# sine_wave_generator.net
KiCad netlist of a schematic drawn in Altium Designer
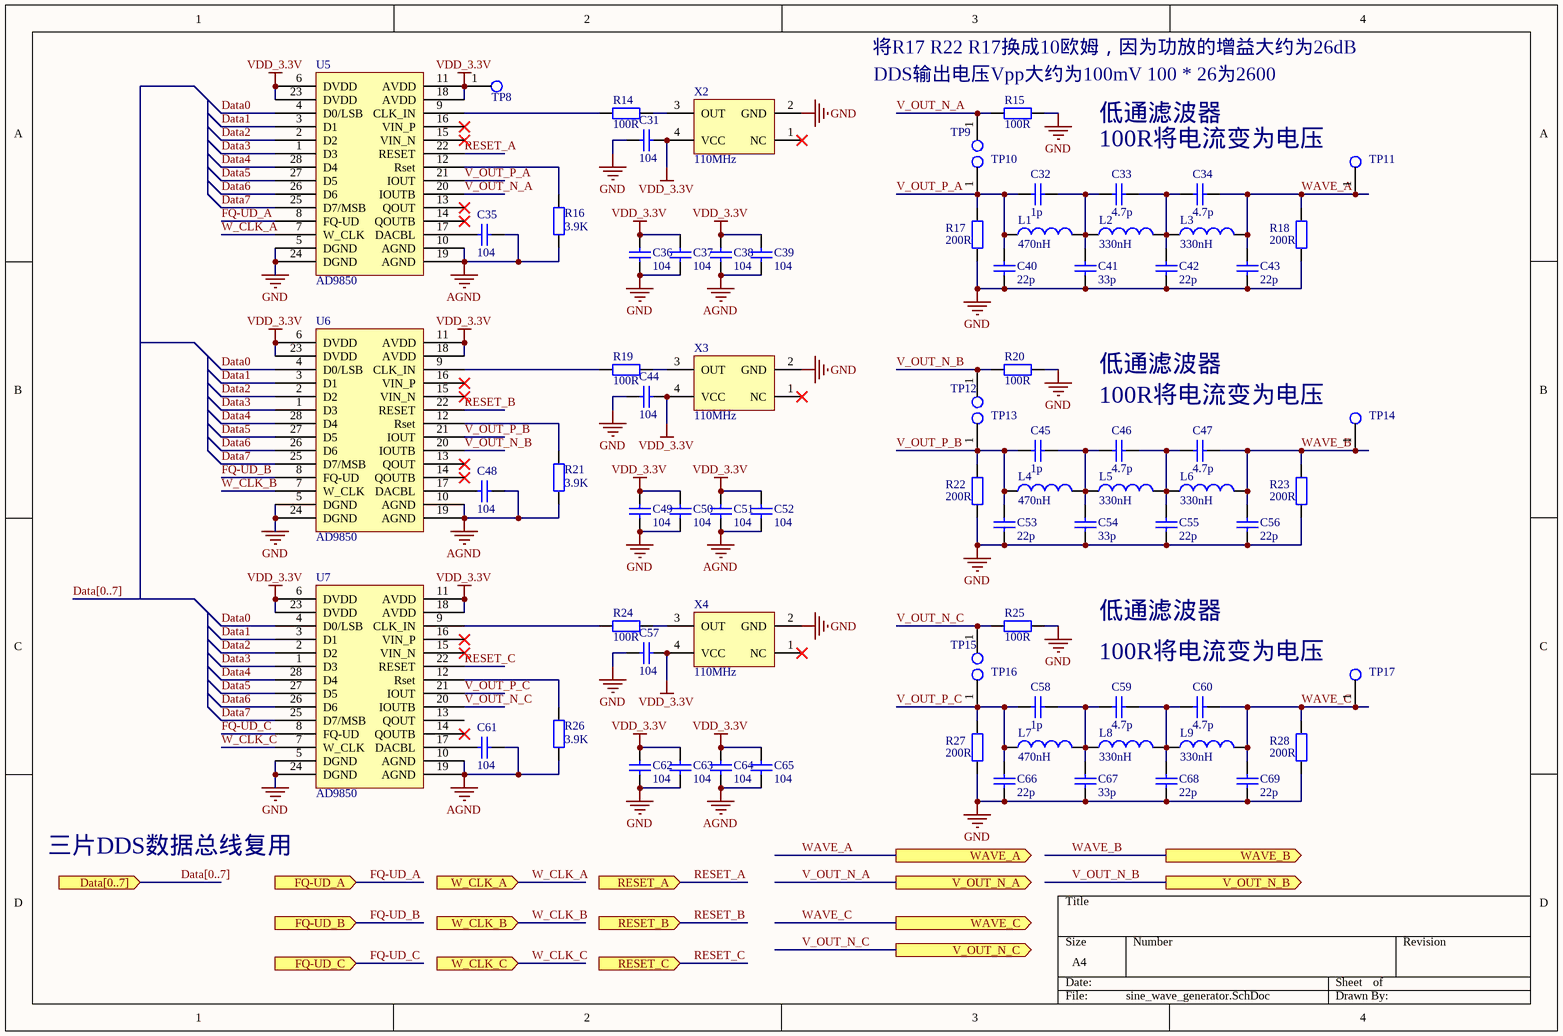
[diagram p0: sine_wave_generator.SchDoc]

(export (version "E")
  (design (tool "Eeschema 10.0.6"))
  (components
    (comp (ref "C31")
      (value "104")
      (footprint "0603")
      (fields (field (name "Comment") "Cap"))
      (libsource (lib "自动化研究所集成库20170318") (part "Cap"))
    )
    (comp (ref "C32")
      (value "1p")
      (footprint "0603")
      (fields (field (name "Comment") "Cap"))
      (libsource (lib "自动化研究所集成库20170318") (part "Cap"))
    )
    (comp (ref "C33")
      (value "4.7p")
      (footprint "0603")
      (fields (field (name "Comment") "Cap"))
      (libsource (lib "自动化研究所集成库20170318") (part "Cap"))
    )
    (comp (ref "C34")
      (value "4.7p")
      (footprint "0603")
      (fields (field (name "Comment") "Cap"))
      (libsource (lib "自动化研究所集成库20170318") (part "Cap"))
    )
    (comp (ref "C35")
      (value "104")
      (footprint "0603")
      (fields (field (name "Comment") "Cap"))
      (libsource (lib "自动化研究所集成库20170318") (part "Cap"))
    )
    (comp (ref "C36")
      (value "104")
      (footprint "0603")
      (fields (field (name "Comment") "Cap"))
      (libsource (lib "自动化研究所集成库20170318") (part "Cap"))
    )
    (comp (ref "C37")
      (value "104")
      (footprint "0603")
      (fields (field (name "Comment") "Cap"))
      (libsource (lib "自动化研究所集成库20170318") (part "Cap"))
    )
    (comp (ref "C38")
      (value "104")
      (footprint "0603")
      (fields (field (name "Comment") "Cap"))
      (libsource (lib "自动化研究所集成库20170318") (part "Cap"))
    )
    (comp (ref "C39")
      (value "104")
      (footprint "0603")
      (fields (field (name "Comment") "Cap"))
      (libsource (lib "自动化研究所集成库20170318") (part "Cap"))
    )
    (comp (ref "C40")
      (value "22p")
      (footprint "0603")
      (fields (field (name "Comment") "Cap"))
      (libsource (lib "自动化研究所集成库20170318") (part "Cap"))
    )
    (comp (ref "C41")
      (value "33p")
      (footprint "0603")
      (fields (field (name "Comment") "Cap"))
      (libsource (lib "自动化研究所集成库20170318") (part "Cap"))
    )
    (comp (ref "C42")
      (value "22p")
      (footprint "0603")
      (fields (field (name "Comment") "Cap"))
      (libsource (lib "自动化研究所集成库20170318") (part "Cap"))
    )
    (comp (ref "C43")
      (value "22p")
      (footprint "0603")
      (fields (field (name "Comment") "Cap"))
      (libsource (lib "自动化研究所集成库20170318") (part "Cap"))
    )
    (comp (ref "C44")
      (value "104")
      (footprint "0603")
      (fields (field (name "Comment") "Cap"))
      (libsource (lib "自动化研究所集成库20170318") (part "Cap"))
    )
    (comp (ref "C45")
      (value "1p")
      (footprint "0603")
      (fields (field (name "Comment") "Cap"))
      (libsource (lib "自动化研究所集成库20170318") (part "Cap"))
    )
    (comp (ref "C46")
      (value "4.7p")
      (footprint "0603")
      (fields (field (name "Comment") "Cap"))
      (libsource (lib "自动化研究所集成库20170318") (part "Cap"))
    )
    (comp (ref "C47")
      (value "4.7p")
      (footprint "0603")
      (fields (field (name "Comment") "Cap"))
      (libsource (lib "自动化研究所集成库20170318") (part "Cap"))
    )
    (comp (ref "C48")
      (value "104")
      (footprint "0603")
      (fields (field (name "Comment") "Cap"))
      (libsource (lib "自动化研究所集成库20170318") (part "Cap"))
    )
    (comp (ref "C49")
      (value "104")
      (footprint "0603")
      (fields (field (name "Comment") "Cap"))
      (libsource (lib "自动化研究所集成库20170318") (part "Cap"))
    )
    (comp (ref "C50")
      (value "104")
      (footprint "0603")
      (fields (field (name "Comment") "Cap"))
      (libsource (lib "自动化研究所集成库20170318") (part "Cap"))
    )
    (comp (ref "C51")
      (value "104")
      (footprint "0603")
      (fields (field (name "Comment") "Cap"))
      (libsource (lib "自动化研究所集成库20170318") (part "Cap"))
    )
    (comp (ref "C52")
      (value "104")
      (footprint "0603")
      (fields (field (name "Comment") "Cap"))
      (libsource (lib "自动化研究所集成库20170318") (part "Cap"))
    )
    (comp (ref "C53")
      (value "22p")
      (footprint "0603")
      (fields (field (name "Comment") "Cap"))
      (libsource (lib "自动化研究所集成库20170318") (part "Cap"))
    )
    (comp (ref "C54")
      (value "33p")
      (footprint "0603")
      (fields (field (name "Comment") "Cap"))
      (libsource (lib "自动化研究所集成库20170318") (part "Cap"))
    )
    (comp (ref "C55")
      (value "22p")
      (footprint "0603")
      (fields (field (name "Comment") "Cap"))
      (libsource (lib "自动化研究所集成库20170318") (part "Cap"))
    )
    (comp (ref "C56")
      (value "22p")
      (footprint "0603")
      (fields (field (name "Comment") "Cap"))
      (libsource (lib "自动化研究所集成库20170318") (part "Cap"))
    )
    (comp (ref "C57")
      (value "104")
      (footprint "0603")
      (fields (field (name "Comment") "Cap"))
      (libsource (lib "自动化研究所集成库20170318") (part "Cap"))
    )
    (comp (ref "C58")
      (value "1p")
      (footprint "0603")
      (fields (field (name "Comment") "Cap"))
      (libsource (lib "自动化研究所集成库20170318") (part "Cap"))
    )
    (comp (ref "C59")
      (value "4.7p")
      (footprint "0603")
      (fields (field (name "Comment") "Cap"))
      (libsource (lib "自动化研究所集成库20170318") (part "Cap"))
    )
    (comp (ref "C60")
      (value "4.7p")
      (footprint "0603")
      (fields (field (name "Comment") "Cap"))
      (libsource (lib "自动化研究所集成库20170318") (part "Cap"))
    )
    (comp (ref "C61")
      (value "104")
      (footprint "0603")
      (fields (field (name "Comment") "Cap"))
      (libsource (lib "自动化研究所集成库20170318") (part "Cap"))
    )
    (comp (ref "C62")
      (value "104")
      (footprint "0603")
      (fields (field (name "Comment") "Cap"))
      (libsource (lib "自动化研究所集成库20170318") (part "Cap"))
    )
    (comp (ref "C63")
      (value "104")
      (footprint "0603")
      (fields (field (name "Comment") "Cap"))
      (libsource (lib "自动化研究所集成库20170318") (part "Cap"))
    )
    (comp (ref "C64")
      (value "104")
      (footprint "0603")
      (fields (field (name "Comment") "Cap"))
      (libsource (lib "自动化研究所集成库20170318") (part "Cap"))
    )
    (comp (ref "C65")
      (value "104")
      (footprint "0603")
      (fields (field (name "Comment") "Cap"))
      (libsource (lib "自动化研究所集成库20170318") (part "Cap"))
    )
    (comp (ref "C66")
      (value "22p")
      (footprint "0603")
      (fields (field (name "Comment") "Cap"))
      (libsource (lib "自动化研究所集成库20170318") (part "Cap"))
    )
    (comp (ref "C67")
      (value "33p")
      (footprint "0603")
      (fields (field (name "Comment") "Cap"))
      (libsource (lib "自动化研究所集成库20170318") (part "Cap"))
    )
    (comp (ref "C68")
      (value "22p")
      (footprint "0603")
      (fields (field (name "Comment") "Cap"))
      (libsource (lib "自动化研究所集成库20170318") (part "Cap"))
    )
    (comp (ref "C69")
      (value "22p")
      (footprint "0603")
      (fields (field (name "Comment") "Cap"))
      (libsource (lib "自动化研究所集成库20170318") (part "Cap"))
    )
    (comp (ref "L1") (value "470nH") (footprint "0805L") (libsource (lib "Spartan") (part "Inductor")))
    (comp (ref "L2") (value "330nH") (footprint "0805L") (libsource (lib "Spartan") (part "Inductor")))
    (comp (ref "L3") (value "330nH") (footprint "0805L") (libsource (lib "Spartan") (part "Inductor")))
    (comp (ref "L4") (value "470nH") (footprint "0805L") (libsource (lib "Spartan") (part "Inductor")))
    (comp (ref "L5") (value "330nH") (footprint "0805L") (libsource (lib "Spartan") (part "Inductor")))
    (comp (ref "L6") (value "330nH") (footprint "0805L") (libsource (lib "Spartan") (part "Inductor")))
    (comp (ref "L7") (value "470nH") (footprint "0805L") (libsource (lib "Spartan") (part "Inductor")))
    (comp (ref "L8") (value "330nH") (footprint "0805L") (libsource (lib "Spartan") (part "Inductor")))
    (comp (ref "L9") (value "330nH") (footprint "0805L") (libsource (lib "Spartan") (part "Inductor")))
    (comp (ref "R14")
      (value "100R")
      (footprint "0603")
      (fields (field (name "Comment") "Res"))
      (libsource (lib "") (part "Res_1"))
    )
    (comp (ref "R15")
      (value "100R")
      (footprint "0603")
      (fields (field (name "Comment") "Res"))
      (libsource (lib "") (part "Res_1"))
    )
    (comp (ref "R16")
      (value "3.9K")
      (footprint "0603")
      (fields (field (name "Comment") "Res"))
      (libsource (lib "自动化研究所集成库20170318") (part "Res"))
    )
    (comp (ref "R17")
      (value "200R")
      (footprint "0603")
      (fields (field (name "Comment") "Res"))
      (libsource (lib "自动化研究所集成库20170318") (part "Res"))
    )
    (comp (ref "R18")
      (value "200R")
      (footprint "0603")
      (fields (field (name "Comment") "Res"))
      (libsource (lib "自动化研究所集成库20170318") (part "Res"))
    )
    (comp (ref "R19")
      (value "100R")
      (footprint "0603")
      (fields (field (name "Comment") "Res"))
      (libsource (lib "") (part "Res_1"))
    )
    (comp (ref "R20")
      (value "100R")
      (footprint "0603")
      (fields (field (name "Comment") "Res"))
      (libsource (lib "") (part "Res_1"))
    )
    (comp (ref "R21")
      (value "3.9K")
      (footprint "0603")
      (fields (field (name "Comment") "Res"))
      (libsource (lib "自动化研究所集成库20170318") (part "Res"))
    )
    (comp (ref "R22")
      (value "200R")
      (footprint "0603")
      (fields (field (name "Comment") "Res"))
      (libsource (lib "自动化研究所集成库20170318") (part "Res"))
    )
    (comp (ref "R23")
      (value "200R")
      (footprint "0603")
      (fields (field (name "Comment") "Res"))
      (libsource (lib "自动化研究所集成库20170318") (part "Res"))
    )
    (comp (ref "R24")
      (value "100R")
      (footprint "0603")
      (fields (field (name "Comment") "Res"))
      (libsource (lib "") (part "Res_1"))
    )
    (comp (ref "R25")
      (value "100R")
      (footprint "0603")
      (fields (field (name "Comment") "Res"))
      (libsource (lib "") (part "Res_1"))
    )
    (comp (ref "R26")
      (value "3.9K")
      (footprint "0603")
      (fields (field (name "Comment") "Res"))
      (libsource (lib "自动化研究所集成库20170318") (part "Res"))
    )
    (comp (ref "R27")
      (value "200R")
      (footprint "0603")
      (fields (field (name "Comment") "Res"))
      (libsource (lib "自动化研究所集成库20170318") (part "Res"))
    )
    (comp (ref "R28")
      (value "200R")
      (footprint "0603")
      (fields (field (name "Comment") "Res"))
      (libsource (lib "自动化研究所集成库20170318") (part "Res"))
    )
    (comp (ref "TP8") (value "testPoint") (footprint "TP_H") (libsource (lib "Spartan") (part "TP")))
    (comp (ref "TP9") (value "testPoint") (footprint "TP_H") (libsource (lib "Spartan") (part "TP")))
    (comp (ref "TP10") (value "testPoint") (footprint "TP_H") (libsource (lib "Spartan") (part "TP")))
    (comp (ref "TP11") (value "testPoint") (footprint "TP_H") (libsource (lib "Spartan") (part "TP")))
    (comp (ref "TP12") (value "testPoint") (footprint "TP_H") (libsource (lib "Spartan") (part "TP")))
    (comp (ref "TP13") (value "testPoint") (footprint "TP_H") (libsource (lib "Spartan") (part "TP")))
    (comp (ref "TP14") (value "testPoint") (footprint "TP_H") (libsource (lib "Spartan") (part "TP")))
    (comp (ref "TP15") (value "testPoint") (footprint "TP_H") (libsource (lib "Spartan") (part "TP")))
    (comp (ref "TP16") (value "testPoint") (footprint "TP_H") (libsource (lib "Spartan") (part "TP")))
    (comp (ref "TP17") (value "testPoint") (footprint "TP_H") (libsource (lib "Spartan") (part "TP")))
    (comp (ref "U5")
      (value "AD9850")
      (footprint "SOP65P780X198-28N")
      (libsource (lib "Dugu") (part "AD9850"))
    )
    (comp (ref "U6")
      (value "AD9850")
      (footprint "SOP65P780X198-28N")
      (libsource (lib "Dugu") (part "AD9850"))
    )
    (comp (ref "U7")
      (value "AD9850")
      (footprint "SOP65P780X198-28N")
      (libsource (lib "Dugu") (part "AD9850"))
    )
    (comp (ref "X2")
      (value "110MHz")
      (footprint "3225")
      (libsource (lib "PulsePower-Buck") (part "Oscillator"))
    )
    (comp (ref "X3")
      (value "110MHz")
      (footprint "3225")
      (libsource (lib "PulsePower-Buck") (part "Oscillator"))
    )
    (comp (ref "X4")
      (value "110MHz")
      (footprint "3225")
      (libsource (lib "PulsePower-Buck") (part "Oscillator"))
    )
  )
  (nets
    (net (code "1") (name "/Data0") (class "Default")
      (node (ref "U5") (pin "4") (pinfunction "D0/LSB_4") (pintype "passive"))
      (node (ref "U6") (pin "4") (pinfunction "D0/LSB_4") (pintype "passive"))
      (node (ref "U7") (pin "4") (pinfunction "D0/LSB_4") (pintype "passive"))
    )
    (net (code "2") (name "/Data1") (class "Default")
      (node (ref "U5") (pin "3") (pinfunction "D1_3") (pintype "passive"))
      (node (ref "U6") (pin "3") (pinfunction "D1_3") (pintype "passive"))
      (node (ref "U7") (pin "3") (pinfunction "D1_3") (pintype "passive"))
    )
    (net (code "3") (name "/Data2") (class "Default")
      (node (ref "U5") (pin "2") (pinfunction "D2_2") (pintype "passive"))
      (node (ref "U6") (pin "2") (pinfunction "D2_2") (pintype "passive"))
      (node (ref "U7") (pin "2") (pinfunction "D2_2") (pintype "passive"))
    )
    (net (code "4") (name "/Data3") (class "Default")
      (node (ref "U5") (pin "1") (pinfunction "D3_1") (pintype "passive"))
      (node (ref "U6") (pin "1") (pinfunction "D3_1") (pintype "passive"))
      (node (ref "U7") (pin "1") (pinfunction "D3_1") (pintype "passive"))
    )
    (net (code "5") (name "/Data4") (class "Default")
      (node (ref "U5") (pin "28") (pinfunction "D4_28") (pintype "passive"))
      (node (ref "U6") (pin "28") (pinfunction "D4_28") (pintype "passive"))
      (node (ref "U7") (pin "28") (pinfunction "D4_28") (pintype "passive"))
    )
    (net (code "6") (name "/Data5") (class "Default")
      (node (ref "U5") (pin "27") (pinfunction "D5_27") (pintype "passive"))
      (node (ref "U6") (pin "27") (pinfunction "D5_27") (pintype "passive"))
      (node (ref "U7") (pin "27") (pinfunction "D5_27") (pintype "passive"))
    )
    (net (code "7") (name "/Data6") (class "Default")
      (node (ref "U5") (pin "26") (pinfunction "D6_26") (pintype "passive"))
      (node (ref "U6") (pin "26") (pinfunction "D6_26") (pintype "passive"))
      (node (ref "U7") (pin "26") (pinfunction "D6_26") (pintype "passive"))
    )
    (net (code "8") (name "/Data7") (class "Default")
      (node (ref "U5") (pin "25") (pinfunction "D7/MSB_25") (pintype "passive"))
      (node (ref "U6") (pin "25") (pinfunction "D7/MSB_25") (pintype "passive"))
      (node (ref "U7") (pin "25") (pinfunction "D7/MSB_25") (pintype "passive"))
    )
    (net (code "10") (name "/FQ-UD_A") (class "Default")
      (node (ref "U5") (pin "8") (pinfunction "FQ-UD_8") (pintype "passive"))
    )
    (net (code "11") (name "/FQ-UD_B") (class "Default")
      (node (ref "U6") (pin "8") (pinfunction "FQ-UD_8") (pintype "passive"))
    )
    (net (code "12") (name "/FQ-UD_C") (class "Default")
      (node (ref "U7") (pin "8") (pinfunction "FQ-UD_8") (pintype "passive"))
    )
    (net (code "13") (name "/RESET_A") (class "Default")
      (node (ref "U5") (pin "22") (pinfunction "RESET_22") (pintype "passive"))
    )
    (net (code "14") (name "/RESET_B") (class "Default")
      (node (ref "U6") (pin "22") (pinfunction "RESET_22") (pintype "passive"))
    )
    (net (code "15") (name "/RESET_C") (class "Default")
      (node (ref "U7") (pin "22") (pinfunction "RESET_22") (pintype "passive"))
    )
    (net (code "16") (name "/V_OUT_N_A") (class "Default")
      (node (ref "R15") (pin "1") (pinfunction "1_1") (pintype "passive"))
      (node (ref "TP9") (pin "1") (pinfunction "1_1") (pintype "passive"))
      (node (ref "U5") (pin "20") (pinfunction "IOUTB_20") (pintype "passive"))
    )
    (net (code "17") (name "/V_OUT_N_B") (class "Default")
      (node (ref "R20") (pin "1") (pinfunction "1_1") (pintype "passive"))
      (node (ref "TP12") (pin "1") (pinfunction "1_1") (pintype "passive"))
      (node (ref "U6") (pin "20") (pinfunction "IOUTB_20") (pintype "passive"))
    )
    (net (code "18") (name "/V_OUT_N_C") (class "Default")
      (node (ref "R25") (pin "1") (pinfunction "1_1") (pintype "passive"))
      (node (ref "TP15") (pin "1") (pinfunction "1_1") (pintype "passive"))
      (node (ref "U7") (pin "20") (pinfunction "IOUTB_20") (pintype "passive"))
    )
    (net (code "19") (name "/V_OUT_P_A") (class "Default")
      (node (ref "C32") (pin "1") (pinfunction "1_1") (pintype "passive"))
      (node (ref "C40") (pin "2") (pinfunction "2_2") (pintype "passive"))
      (node (ref "L1") (pin "1") (pinfunction "1_1") (pintype "passive"))
      (node (ref "R17") (pin "2") (pinfunction "2_2") (pintype "passive"))
      (node (ref "TP10") (pin "1") (pinfunction "1_1") (pintype "passive"))
      (node (ref "U5") (pin "21") (pinfunction "IOUT_21") (pintype "passive"))
    )
    (net (code "20") (name "/V_OUT_P_B") (class "Default")
      (node (ref "C45") (pin "1") (pinfunction "1_1") (pintype "passive"))
      (node (ref "C53") (pin "2") (pinfunction "2_2") (pintype "passive"))
      (node (ref "L4") (pin "1") (pinfunction "1_1") (pintype "passive"))
      (node (ref "R22") (pin "2") (pinfunction "2_2") (pintype "passive"))
      (node (ref "TP13") (pin "1") (pinfunction "1_1") (pintype "passive"))
      (node (ref "U6") (pin "21") (pinfunction "IOUT_21") (pintype "passive"))
    )
    (net (code "21") (name "/V_OUT_P_C") (class "Default")
      (node (ref "C58") (pin "1") (pinfunction "1_1") (pintype "passive"))
      (node (ref "C66") (pin "2") (pinfunction "2_2") (pintype "passive"))
      (node (ref "L7") (pin "1") (pinfunction "1_1") (pintype "passive"))
      (node (ref "R27") (pin "2") (pinfunction "2_2") (pintype "passive"))
      (node (ref "TP16") (pin "1") (pinfunction "1_1") (pintype "passive"))
      (node (ref "U7") (pin "21") (pinfunction "IOUT_21") (pintype "passive"))
    )
    (net (code "22") (name "/WAVE_A") (class "Default")
      (node (ref "C34") (pin "2") (pinfunction "2_2") (pintype "passive"))
      (node (ref "C43") (pin "2") (pinfunction "2_2") (pintype "passive"))
      (node (ref "L3") (pin "2") (pinfunction "2_2") (pintype "passive"))
      (node (ref "R18") (pin "2") (pinfunction "2_2") (pintype "passive"))
      (node (ref "TP11") (pin "1") (pinfunction "1_1") (pintype "passive"))
    )
    (net (code "23") (name "/WAVE_B") (class "Default")
      (node (ref "C47") (pin "2") (pinfunction "2_2") (pintype "passive"))
      (node (ref "C56") (pin "2") (pinfunction "2_2") (pintype "passive"))
      (node (ref "L6") (pin "2") (pinfunction "2_2") (pintype "passive"))
      (node (ref "R23") (pin "2") (pinfunction "2_2") (pintype "passive"))
      (node (ref "TP14") (pin "1") (pinfunction "1_1") (pintype "passive"))
    )
    (net (code "24") (name "/WAVE_C") (class "Default")
      (node (ref "C60") (pin "2") (pinfunction "2_2") (pintype "passive"))
      (node (ref "C69") (pin "2") (pinfunction "2_2") (pintype "passive"))
      (node (ref "L9") (pin "2") (pinfunction "2_2") (pintype "passive"))
      (node (ref "R28") (pin "2") (pinfunction "2_2") (pintype "passive"))
      (node (ref "TP17") (pin "1") (pinfunction "1_1") (pintype "passive"))
    )
    (net (code "25") (name "/W_CLK_A") (class "Default")
      (node (ref "U5") (pin "7") (pinfunction "W_CLK_7") (pintype "passive"))
    )
    (net (code "26") (name "/W_CLK_B") (class "Default")
      (node (ref "U6") (pin "7") (pinfunction "W_CLK_7") (pintype "passive"))
    )
    (net (code "27") (name "/W_CLK_C") (class "Default")
      (node (ref "U7") (pin "7") (pinfunction "W_CLK_7") (pintype "passive"))
    )
    (net (code "28") (name "AGND") (class "Default")
      (node (ref "C35") (pin "2") (pinfunction "2_2") (pintype "passive"))
      (node (ref "C38") (pin "1") (pinfunction "1_1") (pintype "passive"))
      (node (ref "C39") (pin "1") (pinfunction "1_1") (pintype "passive"))
      (node (ref "C48") (pin "2") (pinfunction "2_2") (pintype "passive"))
      (node (ref "C51") (pin "1") (pinfunction "1_1") (pintype "passive"))
      (node (ref "C52") (pin "1") (pinfunction "1_1") (pintype "passive"))
      (node (ref "C61") (pin "1") (pinfunction "1_1") (pintype "passive"))
      (node (ref "C64") (pin "1") (pinfunction "1_1") (pintype "passive"))
      (node (ref "C65") (pin "1") (pinfunction "1_1") (pintype "passive"))
      (node (ref "R16") (pin "1") (pinfunction "1_1") (pintype "passive"))
      (node (ref "R21") (pin "1") (pinfunction "1_1") (pintype "passive"))
      (node (ref "R26") (pin "1") (pinfunction "1_1") (pintype "passive"))
      (node (ref "U5") (pin "10") (pinfunction "AGND_10") (pintype "power_in"))
      (node (ref "U5") (pin "19") (pinfunction "AGND_19") (pintype "passive"))
      (node (ref "U6") (pin "10") (pinfunction "AGND_10") (pintype "power_in"))
      (node (ref "U6") (pin "19") (pinfunction "AGND_19") (pintype "passive"))
      (node (ref "U7") (pin "10") (pinfunction "AGND_10") (pintype "power_in"))
      (node (ref "U7") (pin "19") (pinfunction "AGND_19") (pintype "passive"))
    )
    (net (code "29") (name "GND") (class "Default")
      (node (ref "C31") (pin "1") (pinfunction "1_1") (pintype "passive"))
      (node (ref "C36") (pin "1") (pinfunction "1_1") (pintype "passive"))
      (node (ref "C37") (pin "1") (pinfunction "1_1") (pintype "passive"))
      (node (ref "C40") (pin "1") (pinfunction "1_1") (pintype "passive"))
      (node (ref "C41") (pin "1") (pinfunction "1_1") (pintype "passive"))
      (node (ref "C42") (pin "1") (pinfunction "1_1") (pintype "passive"))
      (node (ref "C43") (pin "1") (pinfunction "1_1") (pintype "passive"))
      (node (ref "C44") (pin "1") (pinfunction "1_1") (pintype "passive"))
      (node (ref "C49") (pin "1") (pinfunction "1_1") (pintype "passive"))
      (node (ref "C50") (pin "1") (pinfunction "1_1") (pintype "passive"))
      (node (ref "C53") (pin "1") (pinfunction "1_1") (pintype "passive"))
      (node (ref "C54") (pin "1") (pinfunction "1_1") (pintype "passive"))
      (node (ref "C55") (pin "1") (pinfunction "1_1") (pintype "passive"))
      (node (ref "C56") (pin "1") (pinfunction "1_1") (pintype "passive"))
      (node (ref "C57") (pin "2") (pinfunction "2_2") (pintype "passive"))
      (node (ref "C62") (pin "1") (pinfunction "1_1") (pintype "passive"))
      (node (ref "C63") (pin "1") (pinfunction "1_1") (pintype "passive"))
      (node (ref "C66") (pin "1") (pinfunction "1_1") (pintype "passive"))
      (node (ref "C67") (pin "1") (pinfunction "1_1") (pintype "passive"))
      (node (ref "C68") (pin "1") (pinfunction "1_1") (pintype "passive"))
      (node (ref "C69") (pin "1") (pinfunction "1_1") (pintype "passive"))
      (node (ref "R15") (pin "2") (pinfunction "2_2") (pintype "passive"))
      (node (ref "R17") (pin "1") (pinfunction "1_1") (pintype "passive"))
      (node (ref "R18") (pin "1") (pinfunction "1_1") (pintype "passive"))
      (node (ref "R20") (pin "2") (pinfunction "2_2") (pintype "passive"))
      (node (ref "R22") (pin "1") (pinfunction "1_1") (pintype "passive"))
      (node (ref "R23") (pin "1") (pinfunction "1_1") (pintype "passive"))
      (node (ref "R25") (pin "2") (pinfunction "2_2") (pintype "passive"))
      (node (ref "R27") (pin "1") (pinfunction "1_1") (pintype "passive"))
      (node (ref "R28") (pin "1") (pinfunction "1_1") (pintype "passive"))
      (node (ref "U5") (pin "24") (pinfunction "DGND_24") (pintype "passive"))
      (node (ref "U5") (pin "5") (pinfunction "DGND_5") (pintype "passive"))
      (node (ref "U6") (pin "24") (pinfunction "DGND_24") (pintype "passive"))
      (node (ref "U6") (pin "5") (pinfunction "DGND_5") (pintype "passive"))
      (node (ref "U7") (pin "24") (pinfunction "DGND_24") (pintype "passive"))
      (node (ref "U7") (pin "5") (pinfunction "DGND_5") (pintype "passive"))
      (node (ref "X2") (pin "2") (pinfunction "GND_2") (pintype "passive"))
      (node (ref "X3") (pin "2") (pinfunction "GND_2") (pintype "passive"))
      (node (ref "X4") (pin "2") (pinfunction "GND_2") (pintype "passive"))
    )
    (net (code "30") (name "Net-(C32-Pad2)") (class "Default")
      (node (ref "C32") (pin "2") (pinfunction "2_2") (pintype "passive"))
      (node (ref "C33") (pin "1") (pinfunction "1_1") (pintype "passive"))
      (node (ref "C41") (pin "2") (pinfunction "2_2") (pintype "passive"))
      (node (ref "L1") (pin "2") (pinfunction "2_2") (pintype "passive"))
      (node (ref "L2") (pin "1") (pinfunction "1_1") (pintype "passive"))
    )
    (net (code "31") (name "Net-(C33-Pad2)") (class "Default")
      (node (ref "C33") (pin "2") (pinfunction "2_2") (pintype "passive"))
      (node (ref "C34") (pin "1") (pinfunction "1_1") (pintype "passive"))
      (node (ref "C42") (pin "2") (pinfunction "2_2") (pintype "passive"))
      (node (ref "L2") (pin "2") (pinfunction "2_2") (pintype "passive"))
      (node (ref "L3") (pin "1") (pinfunction "1_1") (pintype "passive"))
    )
    (net (code "32") (name "Net-(C45-Pad2)") (class "Default")
      (node (ref "C45") (pin "2") (pinfunction "2_2") (pintype "passive"))
      (node (ref "C46") (pin "1") (pinfunction "1_1") (pintype "passive"))
      (node (ref "C54") (pin "2") (pinfunction "2_2") (pintype "passive"))
      (node (ref "L4") (pin "2") (pinfunction "2_2") (pintype "passive"))
      (node (ref "L5") (pin "1") (pinfunction "1_1") (pintype "passive"))
    )
    (net (code "33") (name "Net-(C46-Pad2)") (class "Default")
      (node (ref "C46") (pin "2") (pinfunction "2_2") (pintype "passive"))
      (node (ref "C47") (pin "1") (pinfunction "1_1") (pintype "passive"))
      (node (ref "C55") (pin "2") (pinfunction "2_2") (pintype "passive"))
      (node (ref "L5") (pin "2") (pinfunction "2_2") (pintype "passive"))
      (node (ref "L6") (pin "1") (pinfunction "1_1") (pintype "passive"))
    )
    (net (code "34") (name "Net-(C58-Pad2)") (class "Default")
      (node (ref "C58") (pin "2") (pinfunction "2_2") (pintype "passive"))
      (node (ref "C59") (pin "1") (pinfunction "1_1") (pintype "passive"))
      (node (ref "C67") (pin "2") (pinfunction "2_2") (pintype "passive"))
      (node (ref "L7") (pin "2") (pinfunction "2_2") (pintype "passive"))
      (node (ref "L8") (pin "1") (pinfunction "1_1") (pintype "passive"))
    )
    (net (code "35") (name "Net-(C59-Pad2)") (class "Default")
      (node (ref "C59") (pin "2") (pinfunction "2_2") (pintype "passive"))
      (node (ref "C60") (pin "1") (pinfunction "1_1") (pintype "passive"))
      (node (ref "C68") (pin "2") (pinfunction "2_2") (pintype "passive"))
      (node (ref "L8") (pin "2") (pinfunction "2_2") (pintype "passive"))
      (node (ref "L9") (pin "1") (pinfunction "1_1") (pintype "passive"))
    )
    (net (code "36") (name "Net-(U5-CLK_IN)") (class "Default")
      (node (ref "R14") (pin "1") (pinfunction "1_1") (pintype "passive"))
      (node (ref "U5") (pin "9") (pinfunction "CLK_IN_9") (pintype "passive"))
    )
    (net (code "37") (name "Net-(U5-DACBL)") (class "Default")
      (node (ref "C35") (pin "1") (pinfunction "1_1") (pintype "passive"))
      (node (ref "U5") (pin "17") (pinfunction "DACBL_17") (pintype "passive"))
    )
    (net (code "38") (name "Net-(U5-Rset)") (class "Default")
      (node (ref "R16") (pin "2") (pinfunction "2_2") (pintype "passive"))
      (node (ref "U5") (pin "12") (pinfunction "Rset_12") (pintype "passive"))
    )
    (net (code "39") (name "Net-(U6-CLK_IN)") (class "Default")
      (node (ref "R19") (pin "1") (pinfunction "1_1") (pintype "passive"))
      (node (ref "U6") (pin "9") (pinfunction "CLK_IN_9") (pintype "passive"))
    )
    (net (code "40") (name "Net-(U6-DACBL)") (class "Default")
      (node (ref "C48") (pin "1") (pinfunction "1_1") (pintype "passive"))
      (node (ref "U6") (pin "17") (pinfunction "DACBL_17") (pintype "passive"))
    )
    (net (code "41") (name "Net-(U6-Rset)") (class "Default")
      (node (ref "R21") (pin "2") (pinfunction "2_2") (pintype "passive"))
      (node (ref "U6") (pin "12") (pinfunction "Rset_12") (pintype "passive"))
    )
    (net (code "42") (name "Net-(U7-CLK_IN)") (class "Default")
      (node (ref "R24") (pin "1") (pinfunction "1_1") (pintype "passive"))
      (node (ref "U7") (pin "9") (pinfunction "CLK_IN_9") (pintype "passive"))
    )
    (net (code "43") (name "Net-(U7-DACBL)") (class "Default")
      (node (ref "C61") (pin "2") (pinfunction "2_2") (pintype "passive"))
      (node (ref "U7") (pin "17") (pinfunction "DACBL_17") (pintype "passive"))
    )
    (net (code "44") (name "Net-(U7-Rset)") (class "Default")
      (node (ref "R26") (pin "2") (pinfunction "2_2") (pintype "passive"))
      (node (ref "U7") (pin "12") (pinfunction "Rset_12") (pintype "passive"))
    )
    (net (code "45") (name "Net-(X2-OUT)") (class "Default")
      (node (ref "R14") (pin "2") (pinfunction "2_2") (pintype "passive"))
      (node (ref "X2") (pin "3") (pinfunction "OUT_3") (pintype "passive"))
    )
    (net (code "46") (name "Net-(X3-OUT)") (class "Default")
      (node (ref "R19") (pin "2") (pinfunction "2_2") (pintype "passive"))
      (node (ref "X3") (pin "3") (pinfunction "OUT_3") (pintype "passive"))
    )
    (net (code "47") (name "Net-(X4-OUT)") (class "Default")
      (node (ref "R24") (pin "2") (pinfunction "2_2") (pintype "passive"))
      (node (ref "X4") (pin "3") (pinfunction "OUT_3") (pintype "passive"))
    )
    (net (code "48") (name "VDD_3.3V") (class "Default")
      (node (ref "C31") (pin "2") (pinfunction "2_2") (pintype "passive"))
      (node (ref "C36") (pin "2") (pinfunction "2_2") (pintype "passive"))
      (node (ref "C37") (pin "2") (pinfunction "2_2") (pintype "passive"))
      (node (ref "C38") (pin "2") (pinfunction "2_2") (pintype "passive"))
      (node (ref "C39") (pin "2") (pinfunction "2_2") (pintype "passive"))
      (node (ref "C44") (pin "2") (pinfunction "2_2") (pintype "passive"))
      (node (ref "C49") (pin "2") (pinfunction "2_2") (pintype "passive"))
      (node (ref "C50") (pin "2") (pinfunction "2_2") (pintype "passive"))
      (node (ref "C51") (pin "2") (pinfunction "2_2") (pintype "passive"))
      (node (ref "C52") (pin "2") (pinfunction "2_2") (pintype "passive"))
      (node (ref "C57") (pin "1") (pinfunction "1_1") (pintype "passive"))
      (node (ref "C62") (pin "2") (pinfunction "2_2") (pintype "passive"))
      (node (ref "C63") (pin "2") (pinfunction "2_2") (pintype "passive"))
      (node (ref "C64") (pin "2") (pinfunction "2_2") (pintype "passive"))
      (node (ref "C65") (pin "2") (pinfunction "2_2") (pintype "passive"))
      (node (ref "TP8") (pin "1") (pinfunction "1_1") (pintype "passive"))
      (node (ref "U5") (pin "11") (pinfunction "AVDD_11") (pintype "passive"))
      (node (ref "U5") (pin "18") (pinfunction "AVDD_18") (pintype "passive"))
      (node (ref "U5") (pin "23") (pinfunction "DVDD_23") (pintype "passive"))
      (node (ref "U5") (pin "6") (pinfunction "DVDD_6") (pintype "passive"))
      (node (ref "U6") (pin "11") (pinfunction "AVDD_11") (pintype "passive"))
      (node (ref "U6") (pin "18") (pinfunction "AVDD_18") (pintype "passive"))
      (node (ref "U6") (pin "23") (pinfunction "DVDD_23") (pintype "passive"))
      (node (ref "U6") (pin "6") (pinfunction "DVDD_6") (pintype "passive"))
      (node (ref "U7") (pin "11") (pinfunction "AVDD_11") (pintype "passive"))
      (node (ref "U7") (pin "18") (pinfunction "AVDD_18") (pintype "passive"))
      (node (ref "U7") (pin "23") (pinfunction "DVDD_23") (pintype "passive"))
      (node (ref "U7") (pin "6") (pinfunction "DVDD_6") (pintype "passive"))
      (node (ref "X2") (pin "4") (pinfunction "VCC_4") (pintype "passive"))
      (node (ref "X3") (pin "4") (pinfunction "VCC_4") (pintype "passive"))
      (node (ref "X4") (pin "4") (pinfunction "VCC_4") (pintype "passive"))
    )
    (net (code "49") (name "unconnected-(U5-QOUT-Pad13)") (class "Default")
      (node (ref "U5") (pin "13") (pinfunction "QOUT_13") (pintype "passive+no_connect"))
    )
    (net (code "50") (name "unconnected-(U5-QOUTB-Pad14)") (class "Default")
      (node (ref "U5") (pin "14") (pinfunction "QOUTB_14") (pintype "passive+no_connect"))
    )
    (net (code "51") (name "unconnected-(U5-VIN_N-Pad15)") (class "Default")
      (node (ref "U5") (pin "15") (pinfunction "VIN_N_15") (pintype "passive+no_connect"))
    )
    (net (code "52") (name "unconnected-(U5-VIN_P-Pad16)") (class "Default")
      (node (ref "U5") (pin "16") (pinfunction "VIN_P_16") (pintype "passive+no_connect"))
    )
    (net (code "53") (name "unconnected-(U6-QOUT-Pad13)") (class "Default")
      (node (ref "U6") (pin "13") (pinfunction "QOUT_13") (pintype "passive+no_connect"))
    )
    (net (code "54") (name "unconnected-(U6-QOUTB-Pad14)") (class "Default")
      (node (ref "U6") (pin "14") (pinfunction "QOUTB_14") (pintype "passive+no_connect"))
    )
    (net (code "55") (name "unconnected-(U6-VIN_N-Pad15)") (class "Default")
      (node (ref "U6") (pin "15") (pinfunction "VIN_N_15") (pintype "passive+no_connect"))
    )
    (net (code "56") (name "unconnected-(U6-VIN_P-Pad16)") (class "Default")
      (node (ref "U6") (pin "16") (pinfunction "VIN_P_16") (pintype "passive+no_connect"))
    )
    (net (code "57") (name "unconnected-(U7-QOUT-Pad13)") (class "Default")
      (node (ref "U7") (pin "13") (pinfunction "QOUT_13") (pintype "passive"))
    )
    (net (code "58") (name "unconnected-(U7-QOUTB-Pad14)") (class "Default")
      (node (ref "U7") (pin "14") (pinfunction "QOUTB_14") (pintype "passive+no_connect"))
    )
    (net (code "59") (name "unconnected-(U7-VIN_N-Pad15)") (class "Default")
      (node (ref "U7") (pin "15") (pinfunction "VIN_N_15") (pintype "passive+no_connect"))
    )
    (net (code "60") (name "unconnected-(U7-VIN_P-Pad16)") (class "Default")
      (node (ref "U7") (pin "16") (pinfunction "VIN_P_16") (pintype "passive+no_connect"))
    )
    (net (code "61") (name "unconnected-(X2-NC-Pad1)") (class "Default")
      (node (ref "X2") (pin "1") (pinfunction "NC_1") (pintype "passive+no_connect"))
    )
    (net (code "62") (name "unconnected-(X3-NC-Pad1)") (class "Default")
      (node (ref "X3") (pin "1") (pinfunction "NC_1") (pintype "passive+no_connect"))
    )
    (net (code "63") (name "unconnected-(X4-NC-Pad1)") (class "Default")
      (node (ref "X4") (pin "1") (pinfunction "NC_1") (pintype "passive+no_connect"))
    )
  )
)
